# ATTiny10_Breadboard.net
KiCad netlist of a schematic drawn in EAGLE
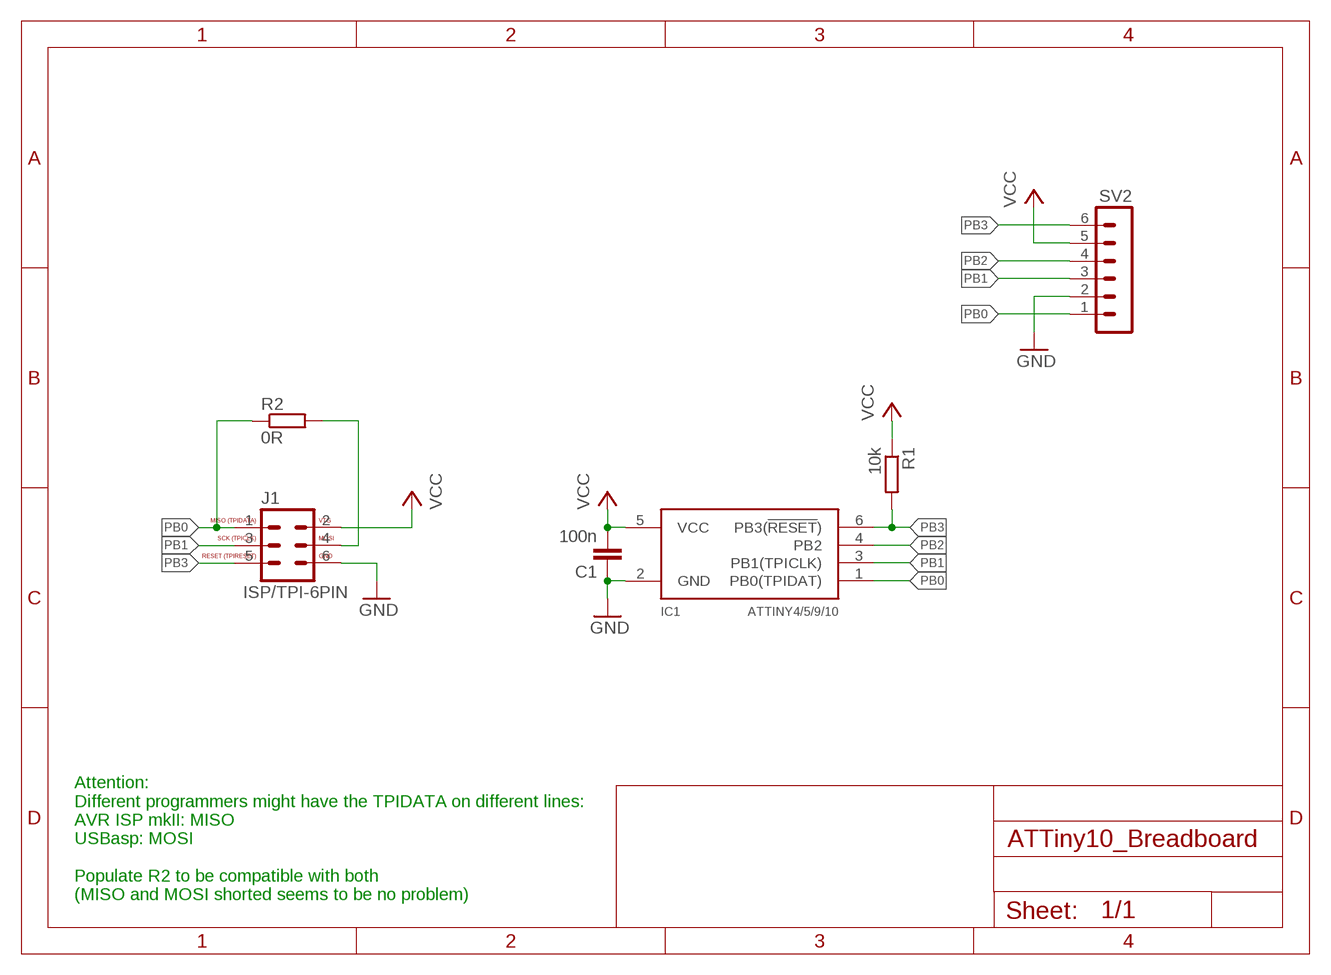
[diagram p0: schematic, sheet 1]

(export (version "E")
  (design (tool "Eeschema 10.0.6"))
  (components
    (comp (ref "C1")
      (value "100n")
      (footprint "eagle-import:C0402")
      (libsource (lib "eagle-import") (part "C-EUC0402"))
    )
    (comp (ref "IC1")
      (value "ATTINY4/5/9/10")
      (footprint "eagle-import:SOT23-6")
      (libsource (lib "eagle-import") (part "ATTINY4/5/9/10"))
    )
    (comp (ref "J1")
      (value "ISP/TPI-6PIN")
      (footprint "eagle-import:ML6")
      (libsource (lib "eagle-import") (part "ISP/TPI-6PIN"))
    )
    (comp (ref "R1")
      (value "10k")
      (footprint "eagle-import:R0402")
      (libsource (lib "eagle-import") (part "R-EU_R0402"))
    )
    (comp (ref "R2")
      (value "0R")
      (footprint "eagle-import:R0402")
      (libsource (lib "eagle-import") (part "R-EU_R0402"))
    )
    (comp (ref "SV2")
      (value "MA06-1")
      (footprint "eagle-import:MA06-1")
      (libsource (lib "eagle-import") (part "MA06-1"))
    )
  )
  (nets
    (net (code "1") (name "GND") (class "Default")
      (node (ref "C1") (pin "1") (pinfunction "1_1") (pintype "passive"))
      (node (ref "IC1") (pin "2") (pinfunction "GND_2") (pintype "bidirectional"))
      (node (ref "J1") (pin "6") (pinfunction "6_6") (pintype "passive"))
      (node (ref "SV2") (pin "2") (pinfunction "2_2") (pintype "passive"))
    )
    (net (code "2") (name "Net-(J1-Pad4)") (class "Default")
      (node (ref "J1") (pin "4") (pinfunction "4_4") (pintype "passive"))
      (node (ref "R2") (pin "2") (pinfunction "2_2") (pintype "passive"))
    )
    (net (code "3") (name "PB0") (class "Default")
      (node (ref "IC1") (pin "1") (pinfunction "PB0(TPIDAT)_1") (pintype "bidirectional"))
      (node (ref "J1") (pin "1") (pinfunction "1_1") (pintype "passive"))
      (node (ref "R2") (pin "1") (pinfunction "1_1") (pintype "passive"))
      (node (ref "SV2") (pin "1") (pinfunction "1_1") (pintype "passive"))
    )
    (net (code "4") (name "PB1") (class "Default")
      (node (ref "IC1") (pin "3") (pinfunction "PB1(TPICLK)_3") (pintype "bidirectional"))
      (node (ref "J1") (pin "3") (pinfunction "3_3") (pintype "passive"))
      (node (ref "SV2") (pin "3") (pinfunction "3_3") (pintype "passive"))
    )
    (net (code "5") (name "PB2") (class "Default")
      (node (ref "IC1") (pin "4") (pinfunction "PB2_4") (pintype "bidirectional"))
      (node (ref "SV2") (pin "4") (pinfunction "4_4") (pintype "passive"))
    )
    (net (code "6") (name "PB3") (class "Default")
      (node (ref "IC1") (pin "6") (pinfunction "PB3(~{RESET})_6") (pintype "bidirectional"))
      (node (ref "J1") (pin "5") (pinfunction "5_5") (pintype "passive"))
      (node (ref "R1") (pin "2") (pinfunction "2_2") (pintype "passive"))
      (node (ref "SV2") (pin "6") (pinfunction "6_6") (pintype "passive"))
    )
    (net (code "7") (name "VCC") (class "Default")
      (node (ref "C1") (pin "2") (pinfunction "2_2") (pintype "passive"))
      (node (ref "IC1") (pin "5") (pinfunction "VCC_5") (pintype "bidirectional"))
      (node (ref "J1") (pin "2") (pinfunction "2_2") (pintype "passive"))
      (node (ref "R1") (pin "1") (pinfunction "1_1") (pintype "passive"))
      (node (ref "SV2") (pin "5") (pinfunction "5_5") (pintype "passive"))
    )
  )
)
